# Power.net
KiCad netlist of a schematic drawn in Altium Designer
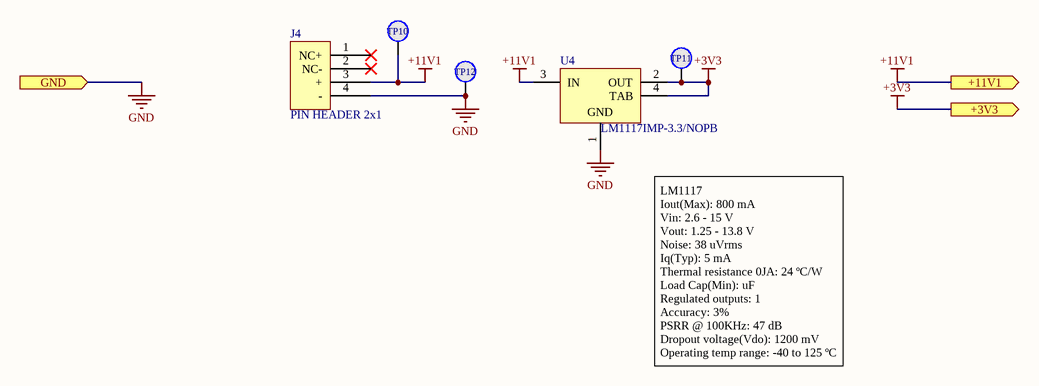
[diagram p0: Power.SchDoc]

(export (version "E")
  (design (tool "Eeschema 10.0.6"))
  (components
    (comp (ref "J4")
      (value "PIN HEADER 2x1")
      (footprint "M20-9950245")
      (description "M20-9950245 Pin Connector")
      (libsource (lib "ControlBoard") (part "M20-9950245"))
    )
    (comp (ref "TP10")
      (value "Test point")
      (footprint "TestPoint")
      (libsource (lib "ControlBoard") (part "TestPoint"))
    )
    (comp (ref "TP11")
      (value "Test point")
      (footprint "TestPoint")
      (libsource (lib "ControlBoard") (part "TestPoint"))
    )
    (comp (ref "TP12")
      (value "Test point")
      (footprint "TestPoint")
      (libsource (lib "ControlBoard") (part "TestPoint"))
    )
    (comp (ref "U4")
      (value "LM1117IMP-3.3/NOPB")
      (footprint "DCY0004A_N")
      (description "800mA Low-Dropout Linear Regulator, 4-pin SOT-223, Pb-Free")
      (fields (field (name "MANUFACTURER") "Texas Instruments"))
      (libsource (lib "ControlBoard") (part "CMP-0062-01631-4"))
    )
  )
  (nets
    (net (code "1") (name "+3V3") (class "Default")
      (node (ref "TP11") (pin "1") (pinfunction "_1_1") (pintype "passive"))
      (node (ref "U4") (pin "2") (pinfunction "OUT_2") (pintype "power_in"))
      (node (ref "U4") (pin "4") (pinfunction "TAB_4") (pintype "power_in"))
    )
    (net (code "2") (name "+11V1") (class "Default")
      (node (ref "J4") (pin "3") (pinfunction "+_3") (pintype "power_in"))
      (node (ref "TP10") (pin "1") (pinfunction "_1_1") (pintype "passive"))
      (node (ref "U4") (pin "3") (pinfunction "IN_3") (pintype "power_in"))
    )
    (net (code "3") (name "GND") (class "Default")
      (node (ref "J4") (pin "4") (pinfunction "-_4") (pintype "power_in"))
      (node (ref "TP12") (pin "1") (pinfunction "_1_1") (pintype "passive"))
      (node (ref "U4") (pin "1") (pinfunction "GND_1") (pintype "power_in"))
    )
    (net (code "4") (name "unconnected-(J4-NC+-Pad1)") (class "Default")
      (node (ref "J4") (pin "1") (pinfunction "NC+_1") (pintype "power_in+no_connect"))
    )
    (net (code "5") (name "unconnected-(J4-NC--Pad2)") (class "Default")
      (node (ref "J4") (pin "2") (pinfunction "NC-_2") (pintype "power_in+no_connect"))
    )
  )
)
